# proc.net
KiCad netlist of a schematic drawn in Altium Designer
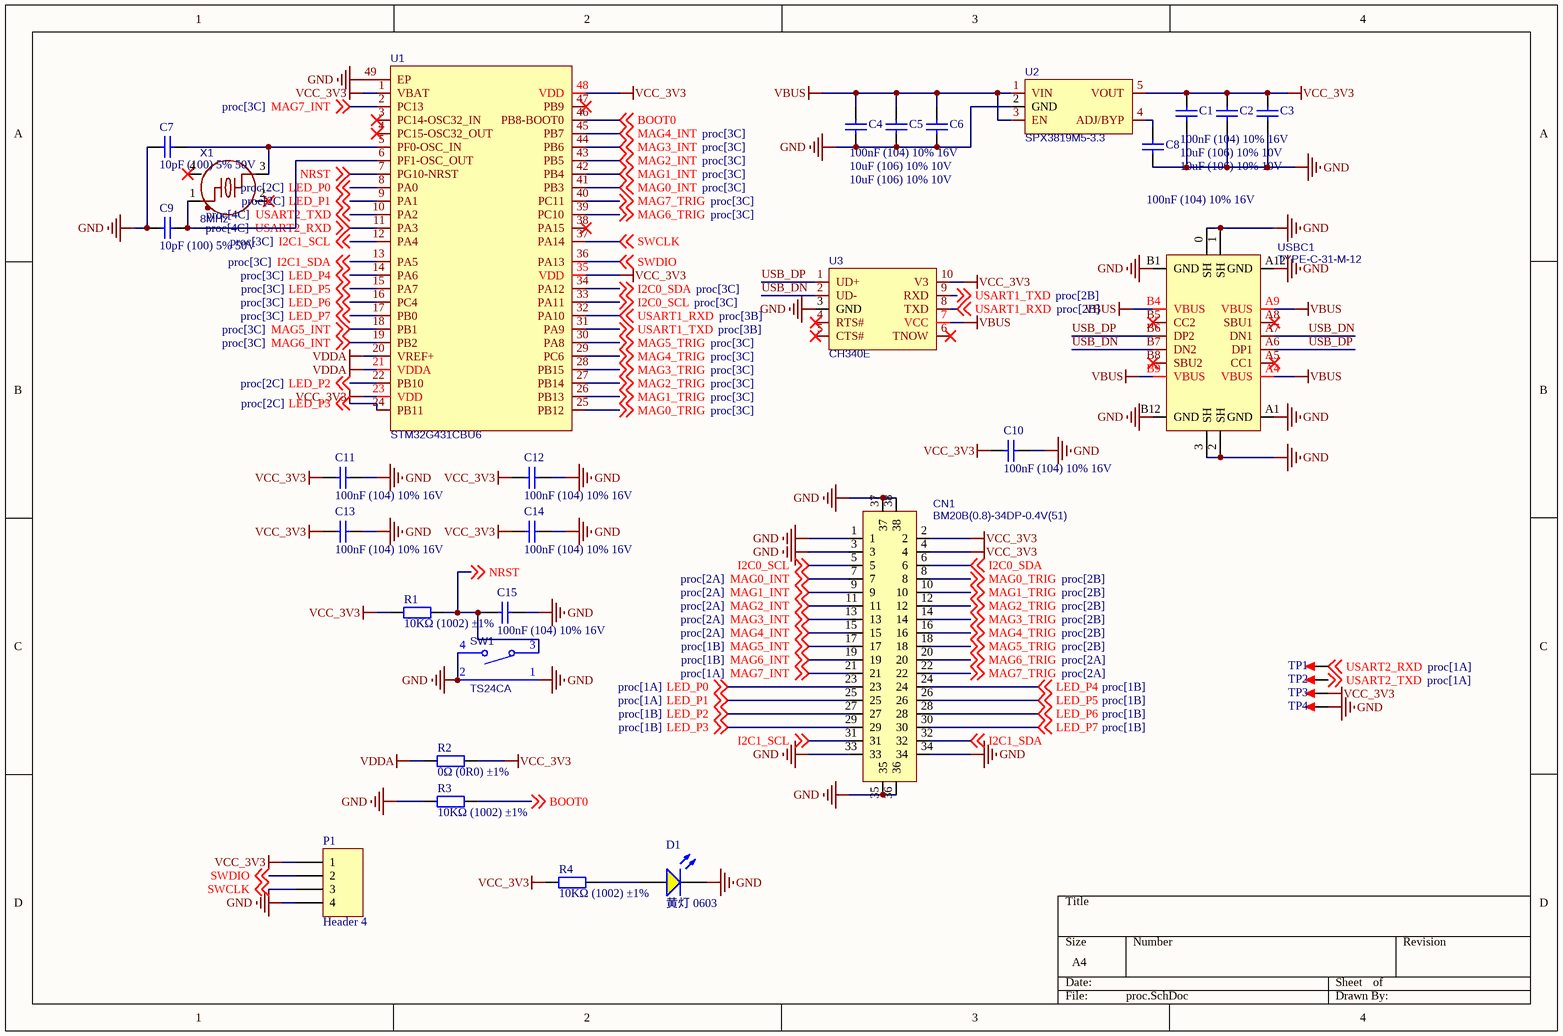
[diagram p0: proc.SchDoc]

(export (version "E")
  (design (tool "Eeschema 10.0.6"))
  (components
    (comp (ref "C1")
      (value "100nF (104) 10% 16V")
      (footprint "LC-0402_C_NOSILK")
      (description "贴片电容")
      (libsource (lib "Miscellaneous Devices LC") (part "0402 100nF (104) 10% 16V"))
    )
    (comp (ref "C2")
      (value "10uF (106) 10% 10V")
      (footprint "LC-0603_C_NOSILK")
      (description "贴片电容")
      (libsource (lib "Miscellaneous Devices LC") (part "0603 10uF (106) 10% 10V"))
    )
    (comp (ref "C3")
      (value "10uF (106) 10% 10V")
      (footprint "LC-0603_C_NOSILK")
      (description "贴片电容")
      (libsource (lib "Miscellaneous Devices LC") (part "0603 10uF (106) 10% 10V"))
    )
    (comp (ref "C4")
      (value "100nF (104) 10% 16V")
      (footprint "LC-0402_C_NOSILK")
      (description "贴片电容")
      (libsource (lib "Miscellaneous Devices LC") (part "0402 100nF (104) 10% 16V"))
    )
    (comp (ref "C5")
      (value "10uF (106) 10% 10V")
      (footprint "LC-0603_C_NOSILK")
      (description "贴片电容")
      (libsource (lib "Miscellaneous Devices LC") (part "0603 10uF (106) 10% 10V"))
    )
    (comp (ref "C6")
      (value "10uF (106) 10% 10V")
      (footprint "LC-0603_C_NOSILK")
      (description "贴片电容")
      (libsource (lib "Miscellaneous Devices LC") (part "0603 10uF (106) 10% 10V"))
    )
    (comp (ref "C7")
      (value "10pF (100) 5% 50V")
      (footprint "LC-0402_C_NOSILK")
      (description "贴片电容")
      (libsource (lib "Miscellaneous Devices LC") (part "0402 10pF (100) 5% 50V"))
    )
    (comp (ref "C8")
      (value "100nF (104) 10% 16V")
      (footprint "LC-0402_C_NOSILK")
      (description "贴片电容")
      (libsource (lib "Miscellaneous Devices LC") (part "0402 100nF (104) 10% 16V"))
    )
    (comp (ref "C9")
      (value "10pF (100) 5% 50V")
      (footprint "LC-0402_C_NOSILK")
      (description "贴片电容")
      (libsource (lib "Miscellaneous Devices LC") (part "0402 10pF (100) 5% 50V"))
    )
    (comp (ref "C10")
      (value "100nF (104) 10% 16V")
      (footprint "LC-0402_C_NOSILK")
      (description "贴片电容")
      (libsource (lib "Miscellaneous Devices LC") (part "0402 100nF (104) 10% 16V"))
    )
    (comp (ref "C11")
      (value "100nF (104) 10% 16V")
      (footprint "LC-0402_C_NOSILK")
      (description "贴片电容")
      (libsource (lib "Miscellaneous Devices LC") (part "0402 100nF (104) 10% 16V"))
    )
    (comp (ref "C12")
      (value "100nF (104) 10% 16V")
      (footprint "LC-0402_C_NOSILK")
      (description "贴片电容")
      (libsource (lib "Miscellaneous Devices LC") (part "0402 100nF (104) 10% 16V"))
    )
    (comp (ref "C13")
      (value "100nF (104) 10% 16V")
      (footprint "LC-0402_C_NOSILK")
      (description "贴片电容")
      (libsource (lib "Miscellaneous Devices LC") (part "0402 100nF (104) 10% 16V"))
    )
    (comp (ref "C14")
      (value "100nF (104) 10% 16V")
      (footprint "LC-0402_C_NOSILK")
      (description "贴片电容")
      (libsource (lib "Miscellaneous Devices LC") (part "0402 100nF (104) 10% 16V"))
    )
    (comp (ref "C15")
      (value "100nF (104) 10% 16V")
      (footprint "LC-0402_C_NOSILK")
      (description "贴片电容")
      (libsource (lib "Miscellaneous Devices LC") (part "0402 100nF (104) 10% 16V"))
    )
    (comp (ref "CN1")
      (value "BM20B(0.8)-34DP-0.4V(51)")
      (footprint "CONN-SMD_34P-P0.40_BM20B-0.8-34DP-0.4V-51")
      (description "0.4mm BTB连接器-34P 公")
      (fields (field (name "BOM_SUPPLIER PART") "C424540") (field (name "CONTRIBUTOR") "LCSC"))
      (libsource (lib "merci") (part "BM20B(0.8)-34DP-0.4V(51)"))
    )
    (comp (ref "D1")
      (value "黄灯 0603")
      (footprint "0603_LED_S1")
      (description "发光二极管")
      (libsource (lib "Miscellaneous Devices LC") (part "0603 黄灯"))
    )
    (comp (ref "P1")
      (value "Header 4")
      (footprint "HDR1X4")
      (description "Header, 4-Pin")
      (fields (field (name "PUBLISHER") "Altium Limited"))
      (libsource (lib "Common Headers") (part "Header 4"))
    )
    (comp (ref "R1")
      (value "10KΩ (1002) ±1%")
      (footprint "LC-0402_R_NOSILK")
      (description "贴片电阻")
      (libsource (lib "Miscellaneous Devices LC") (part "0402 10KΩ (1002) 1%"))
    )
    (comp (ref "R2")
      (value "0Ω (0R0) ±1%")
      (footprint "LC-0402_R_NOSILK")
      (description "贴片电阻")
      (libsource (lib "Miscellaneous Devices LC") (part "0402 0Ω (0R0) 1%"))
    )
    (comp (ref "R3")
      (value "10KΩ (1002) ±1%")
      (footprint "LC-0402_R_NOSILK")
      (description "贴片电阻")
      (libsource (lib "Miscellaneous Devices LC") (part "0402 10KΩ (1002) 1%"))
    )
    (comp (ref "R4")
      (value "10KΩ (1002) ±1%")
      (footprint "LC-0402_R_NOSILK")
      (description "贴片电阻")
      (libsource (lib "Miscellaneous Devices LC") (part "0402 10KΩ (1002) 1%"))
    )
    (comp (ref "SW1")
      (value "TS24CA")
      (footprint "SW-SMD_TS24CA")
      (description "按键")
      (fields (field (name "BOM_SUPPLIER PART") "C393942") (field (name "CONTRIBUTOR") "LCSC"))
      (libsource (lib "merci") (part "TS24CA"))
    )
    (comp (ref "TP1")
      (value "TEST")
      (footprint "TEST 1.6")
      (description "测试点")
      (fields (field (name "版权归属") "源创客"))
      (libsource (lib "merci") (part "TEST"))
    )
    (comp (ref "TP2")
      (value "TEST")
      (footprint "TEST 1.6")
      (description "测试点")
      (fields (field (name "版权归属") "源创客"))
      (libsource (lib "merci") (part "TEST"))
    )
    (comp (ref "TP3")
      (value "TEST")
      (footprint "TEST 1.6")
      (description "测试点")
      (fields (field (name "版权归属") "源创客"))
      (libsource (lib "merci") (part "TEST"))
    )
    (comp (ref "TP4")
      (value "TEST")
      (footprint "TEST 1.6")
      (description "测试点")
      (fields (field (name "版权归属") "源创客"))
      (libsource (lib "merci") (part "TEST"))
    )
    (comp (ref "U1")
      (value "STM32G431CBU6")
      (footprint "UFQFPN-48_L7.0-W7.0-P0.50-BL-EP")
      (fields (field (name "BOM_SUPPLIER PART") "C529356") (field (name "CONTRIBUTOR") "LCSC"))
      (libsource (lib "merci") (part "STM32G431CBU6"))
    )
    (comp (ref "U2")
      (value "SPX3819M5-3.3")
      (footprint "SOT-23-5_L2.9-W1.6-P0.95-LS2.8-BL")
      (description "Vin=16V Vout=3.3V 500mA LDO")
      (fields (field (name "BOM_SUPPLIER PART") "C9900018941") (field (name "CONTRIBUTOR") "lcsc"))
      (libsource (lib "merci") (part "SPX3819M5-3.3"))
    )
    (comp (ref "U3")
      (value "CH340E")
      (footprint "MSOP-10_L3.0-W3.0-P0.50-LS5.0-BL")
      (description "ttl-usb")
      (fields (field (name "BOM_SUPPLIER PART") "C99652"))
      (libsource (lib "merci") (part "CH340E"))
    )
    (comp (ref "USBC1")
      (value "TYPE-C-31-M-12")
      (footprint "USB-C_SMD-TYPE-C-31-M-12")
      (description "贴片type-c母座")
      (fields (field (name "BOM_SUPPLIER PART") "C165948") (field (name "CONTRIBUTOR") "LCSC"))
      (libsource (lib "merci") (part "TYPE-C-31-M-12"))
    )
    (comp (ref "X1")
      (value "8MHz")
      (footprint "CRYSTAL-SMD_4P-L3.2-W2.5-BL")
      (fields
        (field (name "BOM_SUPPLIER PART") "C2933033")
        (field (name "BOM_MANUFACTURER PART") "CF4008M00012T8188031")
        (field (name "CONTRIBUTOR") "LCSC")
      )
      (libsource (lib "merci") (part "8MHz"))
    )
  )
  (nets
    (net (code "1") (name "/USB_DN") (class "Default")
      (node (ref "U3") (pin "2") (pinfunction "UD-_2") (pintype "passive"))
      (node (ref "USBC1") (pin "A7") (pinfunction "DN1_A7") (pintype "passive"))
      (node (ref "USBC1") (pin "B7") (pinfunction "DN2_B7") (pintype "passive"))
    )
    (net (code "2") (name "/USB_DP") (class "Default")
      (node (ref "U3") (pin "1") (pinfunction "UD+_1") (pintype "passive"))
      (node (ref "USBC1") (pin "A6") (pinfunction "DP1_A6") (pintype "passive"))
      (node (ref "USBC1") (pin "B6") (pinfunction "DP2_B6") (pintype "passive"))
    )
    (net (code "3") (name "BOOT0") (class "Default")
      (node (ref "R3") (pin "2") (pinfunction "2_2") (pintype "passive"))
      (node (ref "U1") (pin "46") (pinfunction "PB8-BOOT0_46") (pintype "passive"))
    )
    (net (code "4") (name "GND") (class "Default")
      (node (ref "C1") (pin "1") (pinfunction "1_1") (pintype "passive"))
      (node (ref "C10") (pin "2") (pinfunction "2_2") (pintype "passive"))
      (node (ref "C11") (pin "2") (pinfunction "2_2") (pintype "passive"))
      (node (ref "C12") (pin "2") (pinfunction "2_2") (pintype "passive"))
      (node (ref "C13") (pin "2") (pinfunction "2_2") (pintype "passive"))
      (node (ref "C14") (pin "2") (pinfunction "2_2") (pintype "passive"))
      (node (ref "C15") (pin "2") (pinfunction "2_2") (pintype "passive"))
      (node (ref "C2") (pin "1") (pinfunction "1_1") (pintype "passive"))
      (node (ref "C3") (pin "1") (pinfunction "1_1") (pintype "passive"))
      (node (ref "C4") (pin "1") (pinfunction "1_1") (pintype "passive"))
      (node (ref "C5") (pin "1") (pinfunction "1_1") (pintype "passive"))
      (node (ref "C6") (pin "1") (pinfunction "1_1") (pintype "passive"))
      (node (ref "C7") (pin "1") (pinfunction "1_1") (pintype "passive"))
      (node (ref "C8") (pin "1") (pinfunction "1_1") (pintype "passive"))
      (node (ref "C9") (pin "1") (pinfunction "1_1") (pintype "passive"))
      (node (ref "CN1") (pin "1") (pinfunction "1_1") (pintype "passive"))
      (node (ref "CN1") (pin "3") (pinfunction "3_3") (pintype "passive"))
      (node (ref "CN1") (pin "33") (pinfunction "33_33") (pintype "passive"))
      (node (ref "CN1") (pin "34") (pinfunction "34_34") (pintype "passive"))
      (node (ref "CN1") (pin "35") (pinfunction "35_35") (pintype "passive"))
      (node (ref "CN1") (pin "36") (pinfunction "36_36") (pintype "passive"))
      (node (ref "CN1") (pin "37") (pinfunction "37_37") (pintype "passive"))
      (node (ref "CN1") (pin "38") (pinfunction "38_38") (pintype "passive"))
      (node (ref "D1") (pin "K") (pinfunction "K_K") (pintype "passive"))
      (node (ref "P1") (pin "4") (pinfunction "4_4") (pintype "passive"))
      (node (ref "R3") (pin "1") (pinfunction "1_1") (pintype "passive"))
      (node (ref "SW1") (pin "1") (pinfunction "1_1") (pintype "passive"))
      (node (ref "SW1") (pin "2") (pinfunction "2_2") (pintype "passive"))
      (node (ref "SW1") (pin "4") (pinfunction "4_4") (pintype "passive"))
      (node (ref "TP4") (pin "1") (pinfunction "1_1") (pintype "passive"))
      (node (ref "U1") (pin "49") (pinfunction "EP_49") (pintype "passive"))
      (node (ref "U2") (pin "2") (pinfunction "GND_2") (pintype "passive"))
      (node (ref "U3") (pin "3") (pinfunction "GND_3") (pintype "passive"))
      (node (ref "USBC1") (pin "0") (pinfunction "SH_0") (pintype "passive"))
      (node (ref "USBC1") (pin "1") (pinfunction "SH_1") (pintype "passive"))
      (node (ref "USBC1") (pin "2") (pinfunction "SH_2") (pintype "passive"))
      (node (ref "USBC1") (pin "3") (pinfunction "SH_3") (pintype "passive"))
      (node (ref "USBC1") (pin "A1") (pinfunction "GND_A1") (pintype "passive"))
      (node (ref "USBC1") (pin "A12") (pinfunction "GND_A12") (pintype "passive"))
      (node (ref "USBC1") (pin "B1") (pinfunction "GND_B1") (pintype "passive"))
      (node (ref "USBC1") (pin "B12") (pinfunction "GND_B12") (pintype "passive"))
    )
    (net (code "5") (name "I2C0_SCL") (class "Default")
      (node (ref "CN1") (pin "5") (pinfunction "5_5") (pintype "passive"))
      (node (ref "U1") (pin "33") (pinfunction "PA11_33") (pintype "passive"))
    )
    (net (code "6") (name "I2C0_SDA") (class "Default")
      (node (ref "CN1") (pin "6") (pinfunction "6_6") (pintype "passive"))
      (node (ref "U1") (pin "34") (pinfunction "PA12_34") (pintype "passive"))
    )
    (net (code "7") (name "I2C1_SCL") (class "Default")
      (node (ref "CN1") (pin "31") (pinfunction "31_31") (pintype "passive"))
      (node (ref "U1") (pin "12") (pinfunction "PA4_12") (pintype "passive"))
    )
    (net (code "8") (name "I2C1_SDA") (class "Default")
      (node (ref "CN1") (pin "32") (pinfunction "32_32") (pintype "passive"))
      (node (ref "U1") (pin "13") (pinfunction "PA5_13") (pintype "passive"))
    )
    (net (code "9") (name "LED_P0") (class "Default")
      (node (ref "CN1") (pin "23") (pinfunction "23_23") (pintype "passive"))
      (node (ref "U1") (pin "8") (pinfunction "PA0_8") (pintype "passive"))
    )
    (net (code "10") (name "LED_P1") (class "Default")
      (node (ref "CN1") (pin "25") (pinfunction "25_25") (pintype "passive"))
      (node (ref "U1") (pin "9") (pinfunction "PA1_9") (pintype "passive"))
    )
    (net (code "11") (name "LED_P2") (class "Default")
      (node (ref "CN1") (pin "27") (pinfunction "27_27") (pintype "passive"))
      (node (ref "U1") (pin "22") (pinfunction "PB10_22") (pintype "passive"))
    )
    (net (code "12") (name "LED_P3") (class "Default")
      (node (ref "CN1") (pin "29") (pinfunction "29_29") (pintype "passive"))
      (node (ref "U1") (pin "24") (pinfunction "PB11_24") (pintype "passive"))
    )
    (net (code "13") (name "LED_P4") (class "Default")
      (node (ref "CN1") (pin "24") (pinfunction "24_24") (pintype "passive"))
      (node (ref "U1") (pin "14") (pinfunction "PA6_14") (pintype "passive"))
    )
    (net (code "14") (name "LED_P5") (class "Default")
      (node (ref "CN1") (pin "26") (pinfunction "26_26") (pintype "passive"))
      (node (ref "U1") (pin "15") (pinfunction "PA7_15") (pintype "passive"))
    )
    (net (code "15") (name "LED_P6") (class "Default")
      (node (ref "CN1") (pin "28") (pinfunction "28_28") (pintype "passive"))
      (node (ref "U1") (pin "16") (pinfunction "PC4_16") (pintype "passive"))
    )
    (net (code "16") (name "LED_P7") (class "Default")
      (node (ref "CN1") (pin "30") (pinfunction "30_30") (pintype "passive"))
      (node (ref "U1") (pin "17") (pinfunction "PB0_17") (pintype "passive"))
    )
    (net (code "17") (name "MAG0_INT") (class "Default")
      (node (ref "CN1") (pin "7") (pinfunction "7_7") (pintype "passive"))
      (node (ref "U1") (pin "41") (pinfunction "PB3_41") (pintype "passive"))
    )
    (net (code "18") (name "MAG0_TRIG") (class "Default")
      (node (ref "CN1") (pin "8") (pinfunction "8_8") (pintype "passive"))
      (node (ref "U1") (pin "25") (pinfunction "PB12_25") (pintype "passive"))
    )
    (net (code "19") (name "MAG1_INT") (class "Default")
      (node (ref "CN1") (pin "9") (pinfunction "9_9") (pintype "passive"))
      (node (ref "U1") (pin "42") (pinfunction "PB4_42") (pintype "passive"))
    )
    (net (code "20") (name "MAG1_TRIG") (class "Default")
      (node (ref "CN1") (pin "10") (pinfunction "10_10") (pintype "passive"))
      (node (ref "U1") (pin "26") (pinfunction "PB13_26") (pintype "passive"))
    )
    (net (code "21") (name "MAG2_INT") (class "Default")
      (node (ref "CN1") (pin "11") (pinfunction "11_11") (pintype "passive"))
      (node (ref "U1") (pin "43") (pinfunction "PB5_43") (pintype "passive"))
    )
    (net (code "22") (name "MAG2_TRIG") (class "Default")
      (node (ref "CN1") (pin "12") (pinfunction "12_12") (pintype "passive"))
      (node (ref "U1") (pin "27") (pinfunction "PB14_27") (pintype "passive"))
    )
    (net (code "23") (name "MAG3_INT") (class "Default")
      (node (ref "CN1") (pin "13") (pinfunction "13_13") (pintype "passive"))
      (node (ref "U1") (pin "44") (pinfunction "PB6_44") (pintype "passive"))
    )
    (net (code "24") (name "MAG3_TRIG") (class "Default")
      (node (ref "CN1") (pin "14") (pinfunction "14_14") (pintype "passive"))
      (node (ref "U1") (pin "28") (pinfunction "PB15_28") (pintype "passive"))
    )
    (net (code "25") (name "MAG4_INT") (class "Default")
      (node (ref "CN1") (pin "15") (pinfunction "15_15") (pintype "passive"))
      (node (ref "U1") (pin "45") (pinfunction "PB7_45") (pintype "passive"))
    )
    (net (code "26") (name "MAG4_TRIG") (class "Default")
      (node (ref "CN1") (pin "16") (pinfunction "16_16") (pintype "passive"))
      (node (ref "U1") (pin "29") (pinfunction "PC6_29") (pintype "passive"))
    )
    (net (code "27") (name "MAG5_INT") (class "Default")
      (node (ref "CN1") (pin "17") (pinfunction "17_17") (pintype "passive"))
      (node (ref "U1") (pin "18") (pinfunction "PB1_18") (pintype "passive"))
    )
    (net (code "28") (name "MAG5_TRIG") (class "Default")
      (node (ref "CN1") (pin "18") (pinfunction "18_18") (pintype "passive"))
      (node (ref "U1") (pin "30") (pinfunction "PA8_30") (pintype "passive"))
    )
    (net (code "29") (name "MAG6_INT") (class "Default")
      (node (ref "CN1") (pin "19") (pinfunction "19_19") (pintype "passive"))
      (node (ref "U1") (pin "19") (pinfunction "PB2_19") (pintype "passive"))
    )
    (net (code "30") (name "MAG6_TRIG") (class "Default")
      (node (ref "CN1") (pin "20") (pinfunction "20_20") (pintype "passive"))
      (node (ref "U1") (pin "39") (pinfunction "PC10_39") (pintype "passive"))
    )
    (net (code "31") (name "MAG7_INT") (class "Default")
      (node (ref "CN1") (pin "21") (pinfunction "21_21") (pintype "passive"))
      (node (ref "U1") (pin "2") (pinfunction "PC13_2") (pintype "passive"))
    )
    (net (code "32") (name "MAG7_TRIG") (class "Default")
      (node (ref "CN1") (pin "22") (pinfunction "22_22") (pintype "passive"))
      (node (ref "U1") (pin "40") (pinfunction "PC11_40") (pintype "passive"))
    )
    (net (code "33") (name "NRST") (class "Default")
      (node (ref "C15") (pin "1") (pinfunction "1_1") (pintype "passive"))
      (node (ref "R1") (pin "2") (pinfunction "2_2") (pintype "passive"))
      (node (ref "SW1") (pin "3") (pinfunction "3_3") (pintype "passive"))
      (node (ref "U1") (pin "7") (pinfunction "PG10-NRST_7") (pintype "passive"))
    )
    (net (code "34") (name "Net-(D1-PadA)") (class "Default")
      (node (ref "D1") (pin "A") (pinfunction "A_A") (pintype "passive"))
      (node (ref "R4") (pin "2") (pinfunction "2_2") (pintype "passive"))
    )
    (net (code "35") (name "Net-(U1-PF0-OSC_IN)") (class "Default")
      (node (ref "C7") (pin "2") (pinfunction "2_2") (pintype "passive"))
      (node (ref "U1") (pin "5") (pinfunction "PF0-OSC_IN_5") (pintype "passive"))
      (node (ref "X1") (pin "3") (pinfunction "3_3") (pintype "passive"))
    )
    (net (code "36") (name "Net-(U1-PF1-OSC_OUT)") (class "Default")
      (node (ref "C9") (pin "2") (pinfunction "2_2") (pintype "passive"))
      (node (ref "U1") (pin "6") (pinfunction "PF1-OSC_OUT_6") (pintype "passive"))
      (node (ref "X1") (pin "1") (pinfunction "1_1") (pintype "passive"))
    )
    (net (code "37") (name "Net-(U2-ADJ{slash}BYP)") (class "Default")
      (node (ref "C8") (pin "2") (pinfunction "2_2") (pintype "passive"))
      (node (ref "U2") (pin "4") (pinfunction "ADJ/BYP_4") (pintype "passive"))
    )
    (net (code "38") (name "SWCLK") (class "Default")
      (node (ref "P1") (pin "3") (pinfunction "3_3") (pintype "passive"))
      (node (ref "U1") (pin "37") (pinfunction "PA14_37") (pintype "passive"))
    )
    (net (code "39") (name "SWDIO") (class "Default")
      (node (ref "P1") (pin "2") (pinfunction "2_2") (pintype "passive"))
      (node (ref "U1") (pin "36") (pinfunction "PA13_36") (pintype "passive"))
    )
    (net (code "40") (name "USART1_RXD") (class "Default")
      (node (ref "U1") (pin "32") (pinfunction "PA10_32") (pintype "passive"))
      (node (ref "U3") (pin "8") (pinfunction "TXD_8") (pintype "passive"))
    )
    (net (code "41") (name "USART1_TXD") (class "Default")
      (node (ref "U1") (pin "31") (pinfunction "PA9_31") (pintype "passive"))
      (node (ref "U3") (pin "9") (pinfunction "RXD_9") (pintype "passive"))
    )
    (net (code "42") (name "USART2_RXD") (class "Default")
      (node (ref "TP1") (pin "1") (pinfunction "1_1") (pintype "passive"))
      (node (ref "U1") (pin "11") (pinfunction "PA3_11") (pintype "passive"))
    )
    (net (code "43") (name "USART2_TXD") (class "Default")
      (node (ref "TP2") (pin "1") (pinfunction "1_1") (pintype "passive"))
      (node (ref "U1") (pin "10") (pinfunction "PA2_10") (pintype "passive"))
    )
    (net (code "44") (name "VBUS") (class "Default")
      (node (ref "C4") (pin "2") (pinfunction "2_2") (pintype "passive"))
      (node (ref "C5") (pin "2") (pinfunction "2_2") (pintype "passive"))
      (node (ref "C6") (pin "2") (pinfunction "2_2") (pintype "passive"))
      (node (ref "U2") (pin "1") (pinfunction "VIN_1") (pintype "passive"))
      (node (ref "U2") (pin "3") (pinfunction "EN_3") (pintype "passive"))
      (node (ref "U3") (pin "7") (pinfunction "VCC_7") (pintype "passive"))
      (node (ref "USBC1") (pin "A4") (pinfunction "VBUS_A4") (pintype "passive"))
      (node (ref "USBC1") (pin "A9") (pinfunction "VBUS_A9") (pintype "passive"))
      (node (ref "USBC1") (pin "B4") (pinfunction "VBUS_B4") (pintype "passive"))
      (node (ref "USBC1") (pin "B9") (pinfunction "VBUS_B9") (pintype "passive"))
    )
    (net (code "45") (name "VCC_3V3") (class "Default")
      (node (ref "C1") (pin "2") (pinfunction "2_2") (pintype "passive"))
      (node (ref "C10") (pin "1") (pinfunction "1_1") (pintype "passive"))
      (node (ref "C11") (pin "1") (pinfunction "1_1") (pintype "passive"))
      (node (ref "C12") (pin "1") (pinfunction "1_1") (pintype "passive"))
      (node (ref "C13") (pin "1") (pinfunction "1_1") (pintype "passive"))
      (node (ref "C14") (pin "1") (pinfunction "1_1") (pintype "passive"))
      (node (ref "C2") (pin "2") (pinfunction "2_2") (pintype "passive"))
      (node (ref "C3") (pin "2") (pinfunction "2_2") (pintype "passive"))
      (node (ref "CN1") (pin "2") (pinfunction "2_2") (pintype "passive"))
      (node (ref "CN1") (pin "4") (pinfunction "4_4") (pintype "passive"))
      (node (ref "P1") (pin "1") (pinfunction "1_1") (pintype "passive"))
      (node (ref "R1") (pin "1") (pinfunction "1_1") (pintype "passive"))
      (node (ref "R2") (pin "2") (pinfunction "2_2") (pintype "passive"))
      (node (ref "R4") (pin "1") (pinfunction "1_1") (pintype "passive"))
      (node (ref "TP3") (pin "1") (pinfunction "1_1") (pintype "passive"))
      (node (ref "U1") (pin "1") (pinfunction "VBAT_1") (pintype "passive"))
      (node (ref "U1") (pin "23") (pinfunction "VDD_23") (pintype "passive"))
      (node (ref "U1") (pin "35") (pinfunction "VDD_35") (pintype "passive"))
      (node (ref "U1") (pin "48") (pinfunction "VDD_48") (pintype "passive"))
      (node (ref "U2") (pin "5") (pinfunction "VOUT_5") (pintype "passive"))
      (node (ref "U3") (pin "10") (pinfunction "V3_10") (pintype "passive"))
    )
    (net (code "46") (name "VDDA") (class "Default")
      (node (ref "R2") (pin "1") (pinfunction "1_1") (pintype "passive"))
      (node (ref "U1") (pin "20") (pinfunction "VREF+_20") (pintype "passive"))
      (node (ref "U1") (pin "21") (pinfunction "VDDA_21") (pintype "passive"))
    )
    (net (code "47") (name "unconnected-(U1-PA15-Pad38)") (class "Default")
      (node (ref "U1") (pin "38") (pinfunction "PA15_38") (pintype "passive+no_connect"))
    )
    (net (code "48") (name "unconnected-(U1-PB9-Pad47)") (class "Default")
      (node (ref "U1") (pin "47") (pinfunction "PB9_47") (pintype "passive+no_connect"))
    )
    (net (code "49") (name "unconnected-(U1-PC14-OSC32_IN-Pad3)") (class "Default")
      (node (ref "U1") (pin "3") (pinfunction "PC14-OSC32_IN_3") (pintype "passive+no_connect"))
    )
    (net (code "50") (name "unconnected-(U1-PC15-OSC32_OUT-Pad4)") (class "Default")
      (node (ref "U1") (pin "4") (pinfunction "PC15-OSC32_OUT_4") (pintype "passive+no_connect"))
    )
    (net (code "51") (name "unconnected-(U3-CTS#-Pad5)") (class "Default")
      (node (ref "U3") (pin "5") (pinfunction "CTS#_5") (pintype "passive+no_connect"))
    )
    (net (code "52") (name "unconnected-(U3-RTS#-Pad4)") (class "Default")
      (node (ref "U3") (pin "4") (pinfunction "RTS#_4") (pintype "passive+no_connect"))
    )
    (net (code "53") (name "unconnected-(U3-TNOW-Pad6)") (class "Default")
      (node (ref "U3") (pin "6") (pinfunction "TNOW_6") (pintype "passive+no_connect"))
    )
    (net (code "54") (name "unconnected-(USBC1-CC1-PadA5)") (class "Default")
      (node (ref "USBC1") (pin "A5") (pinfunction "CC1_A5") (pintype "passive+no_connect"))
    )
    (net (code "55") (name "unconnected-(USBC1-CC2-PadB5)") (class "Default")
      (node (ref "USBC1") (pin "B5") (pinfunction "CC2_B5") (pintype "passive+no_connect"))
    )
    (net (code "56") (name "unconnected-(USBC1-SBU1-PadA8)") (class "Default")
      (node (ref "USBC1") (pin "A8") (pinfunction "SBU1_A8") (pintype "passive+no_connect"))
    )
    (net (code "57") (name "unconnected-(USBC1-SBU2-PadB8)") (class "Default")
      (node (ref "USBC1") (pin "B8") (pinfunction "SBU2_B8") (pintype "passive+no_connect"))
    )
    (net (code "58") (name "unconnected-(X1-GND-Pad2)") (class "Default")
      (node (ref "X1") (pin "2") (pinfunction "GND_2") (pintype "passive+no_connect"))
    )
    (net (code "59") (name "unconnected-(X1-GND-Pad4)") (class "Default")
      (node (ref "X1") (pin "4") (pinfunction "GND_4") (pintype "passive+no_connect"))
    )
  )
)
